# P10.net
KiCad netlist of a schematic drawn in EAGLE
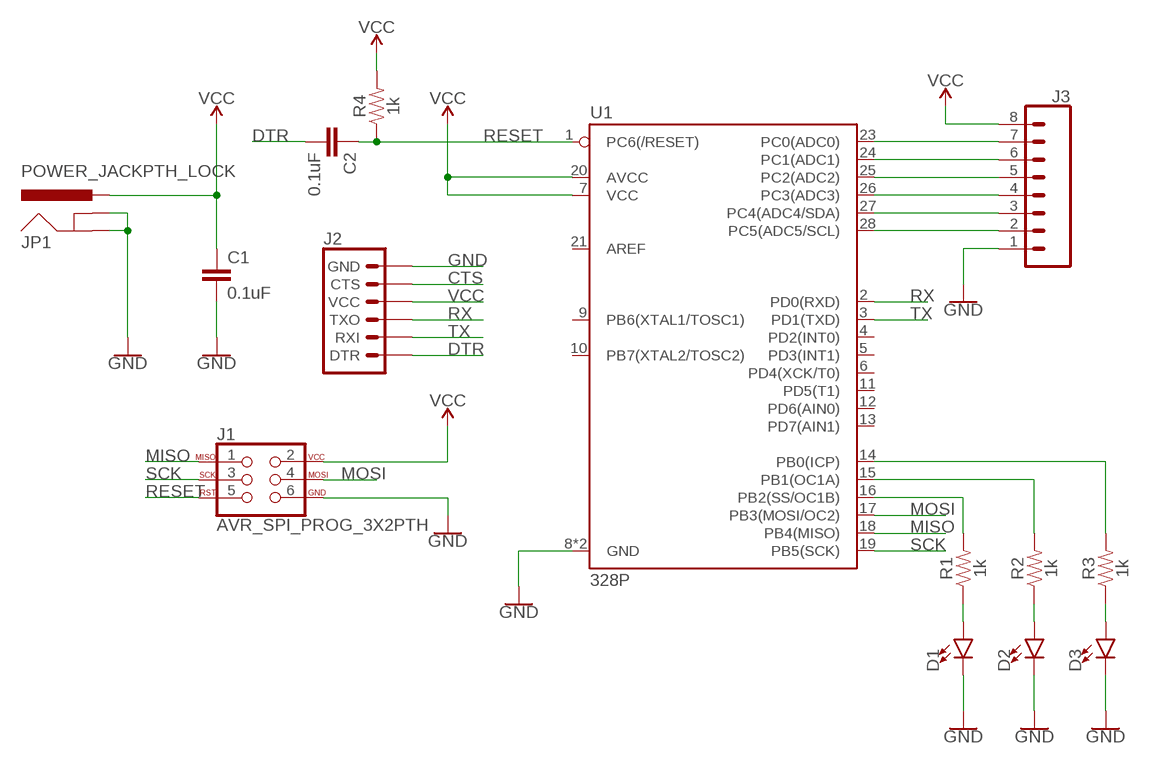
[diagram p0: schematic, sheet 1]

(export (version "E")
  (design (tool "Eeschema 10.0.6"))
  (components
    (comp (ref "C1")
      (value "0.1uF")
      (footprint "eagle-import:CAP-PTH-SMALL")
      (libsource (lib "eagle-import") (part "CAPPTH"))
    )
    (comp (ref "C2")
      (value "0.1uF")
      (footprint "eagle-import:CAP-PTH-SMALL")
      (libsource (lib "eagle-import") (part "CAPPTH"))
    )
    (comp (ref "D1")
      (value "LED5MM")
      (footprint "eagle-import:LED_5MM")
      (libsource (lib "eagle-import") (part "LED5MM"))
    )
    (comp (ref "D2")
      (value "LED5MM")
      (footprint "eagle-import:LED_5MM")
      (libsource (lib "eagle-import") (part "LED5MM"))
    )
    (comp (ref "D3")
      (value "LED5MM")
      (footprint "eagle-import:LED_5MM")
      (libsource (lib "eagle-import") (part "LED5MM"))
    )
    (comp (ref "J1")
      (value "AVR_SPI_PROG_3X2PTH")
      (footprint "eagle-import:2X3")
      (libsource (lib "eagle-import") (part "AVR_SPI_PROG_3X2PTH"))
    )
    (comp (ref "J2")
      (value "6_PIN_SERIAL_TARGET")
      (footprint "eagle-import:1X06")
      (libsource (lib "eagle-import") (part "6_PIN_SERIAL_TARGET"))
    )
    (comp (ref "J3")
      (value "CONN_08\"")
      (footprint "eagle-import:1X08")
      (libsource (lib "eagle-import") (part "CONN_08{dblquote}"))
    )
    (comp (ref "JP1")
      (value "POWER_JACKPTH_LOCK")
      (footprint "eagle-import:POWER_JACK_PTH_LOCK")
      (libsource (lib "eagle-import") (part "POWER_JACKPTH_LOCK"))
    )
    (comp (ref "R1")
      (value "1k")
      (footprint "eagle-import:AXIAL-0.3")
      (libsource (lib "eagle-import") (part "1KOHM-HORIZ-1/4W-1%"))
    )
    (comp (ref "R2")
      (value "1k")
      (footprint "eagle-import:AXIAL-0.3")
      (libsource (lib "eagle-import") (part "1KOHM-HORIZ-1/4W-1%"))
    )
    (comp (ref "R3")
      (value "1k")
      (footprint "eagle-import:AXIAL-0.3")
      (libsource (lib "eagle-import") (part "1KOHM-HORIZ-1/4W-1%"))
    )
    (comp (ref "R4")
      (value "1k")
      (footprint "eagle-import:AXIAL-0.3")
      (libsource (lib "eagle-import") (part "1KOHM-HORIZ-1/4W-1%"))
    )
    (comp (ref "U1")
      (value "328P")
      (footprint "eagle-import:DIP28")
      (libsource (lib "eagle-import") (part "ATMEGA328P_PDIP"))
    )
  )
  (nets
    (net (code "1") (name "/CTS") (class "Default")
      (node (ref "J2") (pin "5") (pinfunction "CTS_5") (pintype "passive"))
    )
    (net (code "2") (name "/DTR") (class "Default")
      (node (ref "C2") (pin "2") (pinfunction "2_2") (pintype "passive"))
      (node (ref "J2") (pin "1") (pinfunction "DTR_1") (pintype "passive"))
    )
    (net (code "3") (name "/MISO") (class "Default")
      (node (ref "J1") (pin "1") (pinfunction "1_1") (pintype "passive"))
      (node (ref "U1") (pin "18") (pinfunction "PB4(MISO)_18") (pintype "bidirectional"))
    )
    (net (code "4") (name "/MOSI") (class "Default")
      (node (ref "J1") (pin "4") (pinfunction "4_4") (pintype "passive"))
      (node (ref "U1") (pin "17") (pinfunction "PB3(MOSI/OC2)_17") (pintype "bidirectional"))
    )
    (net (code "5") (name "/RESET") (class "Default")
      (node (ref "C2") (pin "1") (pinfunction "1_1") (pintype "passive"))
      (node (ref "J1") (pin "5") (pinfunction "5_5") (pintype "passive"))
      (node (ref "R4") (pin "P$1") (pinfunction "1_P$1") (pintype "passive"))
      (node (ref "U1") (pin "1") (pinfunction "PC6(/RESET)_1") (pintype "bidirectional"))
    )
    (net (code "6") (name "/RX") (class "Default")
      (node (ref "J2") (pin "3") (pinfunction "TXO_3") (pintype "passive"))
      (node (ref "U1") (pin "2") (pinfunction "PD0(RXD)_2") (pintype "bidirectional"))
    )
    (net (code "7") (name "/SCK") (class "Default")
      (node (ref "J1") (pin "3") (pinfunction "3_3") (pintype "passive"))
      (node (ref "U1") (pin "19") (pinfunction "PB5(SCK)_19") (pintype "bidirectional"))
    )
    (net (code "8") (name "/TX") (class "Default")
      (node (ref "J2") (pin "2") (pinfunction "RXI_2") (pintype "passive"))
      (node (ref "U1") (pin "3") (pinfunction "PD1(TXD)_3") (pintype "bidirectional"))
    )
    (net (code "9") (name "GND") (class "Default")
      (node (ref "C1") (pin "2") (pinfunction "2_2") (pintype "passive"))
      (node (ref "D1") (pin "K") (pinfunction "C_K") (pintype "passive"))
      (node (ref "D2") (pin "K") (pinfunction "C_K") (pintype "passive"))
      (node (ref "D3") (pin "K") (pinfunction "C_K") (pintype "passive"))
      (node (ref "J1") (pin "6") (pinfunction "6_6") (pintype "passive"))
      (node (ref "J2") (pin "6") (pinfunction "GND_6") (pintype "passive"))
      (node (ref "J3") (pin "1") (pinfunction "1_1") (pintype "passive"))
      (node (ref "JP1") (pin "GND") (pinfunction "GND_GND") (pintype "bidirectional"))
      (node (ref "JP1") (pin "GNDBREAK") (pinfunction "GNDBREAK_GNDBREAK") (pintype "bidirectional"))
      (node (ref "U1") (pin "22") (pinfunction "GND_22") (pintype "bidirectional"))
      (node (ref "U1") (pin "8") (pinfunction "GND_8") (pintype "bidirectional"))
    )
    (net (code "10") (name "Net-(R1-1)") (class "Default")
      (node (ref "D1") (pin "A") (pinfunction "A_A") (pintype "passive"))
      (node (ref "R1") (pin "P$1") (pinfunction "1_P$1") (pintype "passive"))
    )
    (net (code "11") (name "Net-(R1-2)") (class "Default")
      (node (ref "R1") (pin "P$2") (pinfunction "2_P$2") (pintype "passive"))
      (node (ref "U1") (pin "16") (pinfunction "PB2(SS/OC1B)_16") (pintype "bidirectional"))
    )
    (net (code "12") (name "Net-(R2-1)") (class "Default")
      (node (ref "D2") (pin "A") (pinfunction "A_A") (pintype "passive"))
      (node (ref "R2") (pin "P$1") (pinfunction "1_P$1") (pintype "passive"))
    )
    (net (code "13") (name "Net-(R2-2)") (class "Default")
      (node (ref "R2") (pin "P$2") (pinfunction "2_P$2") (pintype "passive"))
      (node (ref "U1") (pin "15") (pinfunction "PB1(OC1A)_15") (pintype "bidirectional"))
    )
    (net (code "14") (name "Net-(R3-1)") (class "Default")
      (node (ref "D3") (pin "A") (pinfunction "A_A") (pintype "passive"))
      (node (ref "R3") (pin "P$1") (pinfunction "1_P$1") (pintype "passive"))
    )
    (net (code "15") (name "Net-(R3-2)") (class "Default")
      (node (ref "R3") (pin "P$2") (pinfunction "2_P$2") (pintype "passive"))
      (node (ref "U1") (pin "14") (pinfunction "PB0(ICP)_14") (pintype "bidirectional"))
    )
    (net (code "16") (name "Net-(U1-PC0(ADC0))") (class "Default")
      (node (ref "J3") (pin "7") (pinfunction "7_7") (pintype "passive"))
      (node (ref "U1") (pin "23") (pinfunction "PC0(ADC0)_23") (pintype "bidirectional"))
    )
    (net (code "17") (name "Net-(U1-PC1(ADC1))") (class "Default")
      (node (ref "J3") (pin "6") (pinfunction "6_6") (pintype "passive"))
      (node (ref "U1") (pin "24") (pinfunction "PC1(ADC1)_24") (pintype "bidirectional"))
    )
    (net (code "18") (name "Net-(U1-PC2(ADC2))") (class "Default")
      (node (ref "J3") (pin "5") (pinfunction "5_5") (pintype "passive"))
      (node (ref "U1") (pin "25") (pinfunction "PC2(ADC2)_25") (pintype "bidirectional"))
    )
    (net (code "19") (name "Net-(U1-PC3(ADC3))") (class "Default")
      (node (ref "J3") (pin "4") (pinfunction "4_4") (pintype "passive"))
      (node (ref "U1") (pin "26") (pinfunction "PC3(ADC3)_26") (pintype "bidirectional"))
    )
    (net (code "20") (name "Net-(U1-PC4(ADC4{slash}SDA))") (class "Default")
      (node (ref "J3") (pin "3") (pinfunction "3_3") (pintype "passive"))
      (node (ref "U1") (pin "27") (pinfunction "PC4(ADC4/SDA)_27") (pintype "bidirectional"))
    )
    (net (code "21") (name "Net-(U1-PC5(ADC5{slash}SCL))") (class "Default")
      (node (ref "J3") (pin "2") (pinfunction "2_2") (pintype "passive"))
      (node (ref "U1") (pin "28") (pinfunction "PC5(ADC5/SCL)_28") (pintype "bidirectional"))
    )
    (net (code "22") (name "VCC") (class "Default")
      (node (ref "C1") (pin "1") (pinfunction "1_1") (pintype "passive"))
      (node (ref "J1") (pin "2") (pinfunction "2_2") (pintype "passive"))
      (node (ref "J2") (pin "4") (pinfunction "VCC_4") (pintype "passive"))
      (node (ref "J3") (pin "8") (pinfunction "8_8") (pintype "passive"))
      (node (ref "JP1") (pin "PWR") (pinfunction "PWR_PWR") (pintype "bidirectional"))
      (node (ref "R4") (pin "P$2") (pinfunction "2_P$2") (pintype "passive"))
      (node (ref "U1") (pin "20") (pinfunction "AVCC_20") (pintype "bidirectional"))
      (node (ref "U1") (pin "7") (pinfunction "VCC_7") (pintype "bidirectional"))
    )
    (net (code "23") (name "unconnected-(U1-AREF-Pad21)") (class "Default")
      (node (ref "U1") (pin "21") (pinfunction "AREF_21") (pintype "bidirectional"))
    )
    (net (code "24") (name "unconnected-(U1-PB6(XTAL1{slash}TOSC1)-Pad9)") (class "Default")
      (node (ref "U1") (pin "9") (pinfunction "PB6(XTAL1/TOSC1)_9") (pintype "bidirectional"))
    )
    (net (code "25") (name "unconnected-(U1-PB7(XTAL2{slash}TOSC2)-Pad10)") (class "Default")
      (node (ref "U1") (pin "10") (pinfunction "PB7(XTAL2/TOSC2)_10") (pintype "bidirectional"))
    )
    (net (code "26") (name "unconnected-(U1-PD2(INT0)-Pad4)") (class "Default")
      (node (ref "U1") (pin "4") (pinfunction "PD2(INT0)_4") (pintype "bidirectional"))
    )
    (net (code "27") (name "unconnected-(U1-PD3(INT1)-Pad5)") (class "Default")
      (node (ref "U1") (pin "5") (pinfunction "PD3(INT1)_5") (pintype "bidirectional"))
    )
    (net (code "28") (name "unconnected-(U1-PD4(XCK{slash}T0)-Pad6)") (class "Default")
      (node (ref "U1") (pin "6") (pinfunction "PD4(XCK/T0)_6") (pintype "bidirectional"))
    )
    (net (code "29") (name "unconnected-(U1-PD5(T1)-Pad11)") (class "Default")
      (node (ref "U1") (pin "11") (pinfunction "PD5(T1)_11") (pintype "bidirectional"))
    )
    (net (code "30") (name "unconnected-(U1-PD6(AIN0)-Pad12)") (class "Default")
      (node (ref "U1") (pin "12") (pinfunction "PD6(AIN0)_12") (pintype "bidirectional"))
    )
    (net (code "31") (name "unconnected-(U1-PD7(AIN1)-Pad13)") (class "Default")
      (node (ref "U1") (pin "13") (pinfunction "PD7(AIN1)_13") (pintype "bidirectional"))
    )
  )
)
